# Sheet1.net
KiCad netlist of a schematic drawn in Altium Designer
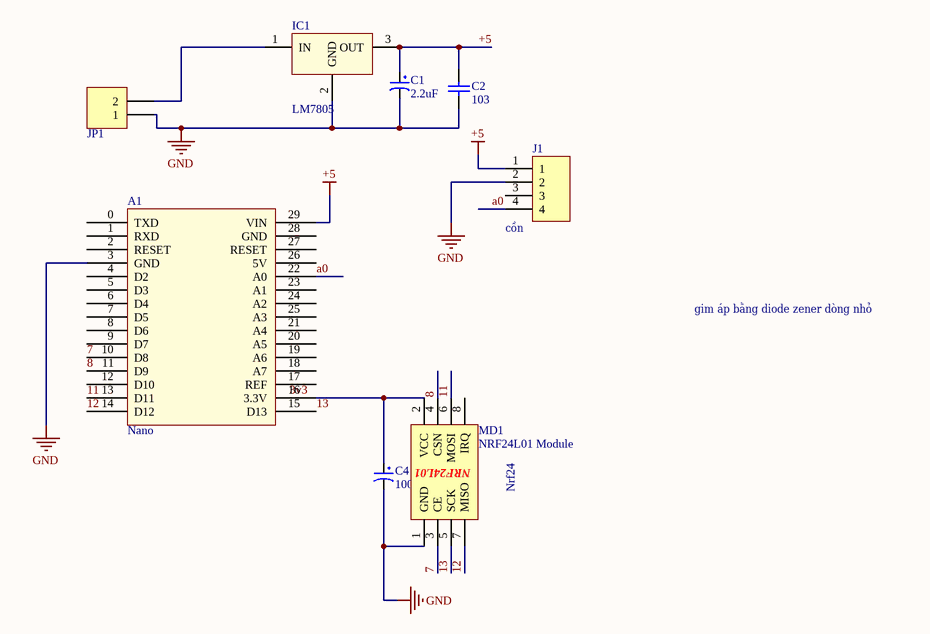
[diagram p0: Sheet1.SchDoc]

(export (version "E")
  (design (tool "Eeschema 10.0.6"))
  (components
    (comp (ref "A1")
      (value "Nano")
      (footprint "Arduino nano")
      (libsource (lib "Altium_Lib_by_KhueNguyenCreator") (part "Arduino Nano"))
    )
    (comp (ref "C1")
      (value "2.2uF")
      (footprint "tu hoa 4mm")
      (description "Cắm")
      (libsource (lib "Altium_Lib_by_KhueNguyenCreator") (part "Tu Hoa 2.2uF 50V 4x7"))
    )
    (comp (ref "C2")
      (value "103")
      (footprint "tu gom")
      (description "Cắm")
      (libsource (lib "Altium_Lib_by_KhueNguyenCreator") (part "Tu gom 103 50V"))
    )
    (comp (ref "C4")
      (value "100uF")
      (footprint "tu hoa 6.5mm")
      (description "Cắm")
      (libsource (lib "Altium_Lib_by_KhueNguyenCreator") (part "Tu Hoa 100uF 35V 6x8"))
    )
    (comp (ref "IC1")
      (value "LM7805")
      (footprint "QTO-220")
      (description "On ap +, from + 5 to + 24VDC")
      (libsource (lib "syhaunguyen") (part "LM78xx"))
    )
    (comp (ref "J1")
      (value "~")
      (footprint "CON4_50_653004117322_TH_RA")
      (description "4 Pins, 1 Row 1.25mm Pitch, right angle Connector, male")
      (fields (field (name "MANUFACTURER PART NUMBER") "653004117322") (field (name "MANUFACTURER") "JST"))
      (libsource (lib "Altium_Lib_by_KhueNguyenCreator") (part "CON-PLG_4X1-50-RA-TH"))
    )
    (comp (ref "JP1")
      (value "Header 2_1")
      (footprint "HED2")
      (description "Header, 2-Pin")
      (fields (field (name "MANUFACTURER") "Generic Components"))
      (libsource (lib "syhaunguyen") (part "Header 2_1"))
    )
    (comp (ref "MD1")
      (value "NRF24L01 Module")
      (footprint "NRF24L01")
      (libsource (lib "Altium_Lib_by_KhueNguyenCreator") (part "NRF24L01 Module"))
    )
  )
  (nets
    (net (code "1") (name "+5") (class "Default")
      (node (ref "A1") (pin "29") (pinfunction "VIN_29") (pintype "passive"))
      (node (ref "C1") (pin "1") (pinfunction "1_1") (pintype "passive"))
      (node (ref "C2") (pin "1") (pinfunction "1_1") (pintype "passive"))
      (node (ref "IC1") (pin "3") (pinfunction "OUT_3") (pintype "passive"))
      (node (ref "J1") (pin "1") (pinfunction "1_1") (pintype "passive"))
    )
    (net (code "3") (name "/7") (class "Default")
      (node (ref "A1") (pin "10") (pinfunction "D8_10") (pintype "passive"))
      (node (ref "MD1") (pin "3") (pinfunction "CE_3") (pintype "passive"))
    )
    (net (code "4") (name "/8") (class "Default")
      (node (ref "A1") (pin "11") (pinfunction "D9_11") (pintype "passive"))
      (node (ref "MD1") (pin "4") (pinfunction "CSN_4") (pintype "passive"))
    )
    (net (code "5") (name "/11") (class "Default")
      (node (ref "A1") (pin "13") (pinfunction "D11_13") (pintype "passive"))
      (node (ref "MD1") (pin "6") (pinfunction "MOSI_6") (pintype "passive"))
    )
    (net (code "6") (name "/12") (class "Default")
      (node (ref "A1") (pin "14") (pinfunction "D12_14") (pintype "passive"))
      (node (ref "MD1") (pin "7") (pinfunction "MISO_7") (pintype "passive"))
    )
    (net (code "7") (name "/13") (class "Default")
      (node (ref "A1") (pin "15") (pinfunction "D13_15") (pintype "passive"))
      (node (ref "MD1") (pin "5") (pinfunction "SCK_5") (pintype "passive"))
    )
    (net (code "8") (name "/a0") (class "Default")
      (node (ref "A1") (pin "22") (pinfunction "A0_22") (pintype "passive"))
      (node (ref "J1") (pin "4") (pinfunction "4_4") (pintype "passive"))
    )
    (net (code "9") (name "GND") (class "Default")
      (node (ref "A1") (pin "3") (pinfunction "GND_3") (pintype "passive"))
      (node (ref "C1") (pin "2") (pinfunction "2_2") (pintype "passive"))
      (node (ref "C2") (pin "2") (pinfunction "2_2") (pintype "passive"))
      (node (ref "C4") (pin "2") (pinfunction "2_2") (pintype "passive"))
      (node (ref "IC1") (pin "2") (pinfunction "GND_2") (pintype "passive"))
      (node (ref "J1") (pin "2") (pinfunction "2_2") (pintype "passive"))
      (node (ref "JP1") (pin "1") (pinfunction "1_1") (pintype "passive"))
      (node (ref "MD1") (pin "1") (pinfunction "GND_1") (pintype "passive"))
    )
    (net (code "10") (name "Net-(A1-3.3V)") (class "Default")
      (node (ref "A1") (pin "16") (pinfunction "3.3V_16") (pintype "passive"))
      (node (ref "C4") (pin "1") (pinfunction "1_1") (pintype "passive"))
      (node (ref "MD1") (pin "2") (pinfunction "VCC_2") (pintype "passive"))
    )
    (net (code "11") (name "Net-(IC1-IN)") (class "Default")
      (node (ref "IC1") (pin "1") (pinfunction "IN_1") (pintype "passive"))
      (node (ref "JP1") (pin "2") (pinfunction "2_2") (pintype "passive"))
    )
    (net (code "12") (name "unconnected-(A1-5V-Pad26)") (class "Default")
      (node (ref "A1") (pin "26") (pinfunction "5V_26") (pintype "passive"))
    )
    (net (code "13") (name "unconnected-(A1-A1-Pad23)") (class "Default")
      (node (ref "A1") (pin "23") (pinfunction "A1_23") (pintype "passive"))
    )
    (net (code "14") (name "unconnected-(A1-A2-Pad24)") (class "Default")
      (node (ref "A1") (pin "24") (pinfunction "A2_24") (pintype "passive"))
    )
    (net (code "15") (name "unconnected-(A1-A3-Pad25)") (class "Default")
      (node (ref "A1") (pin "25") (pinfunction "A3_25") (pintype "passive"))
    )
    (net (code "16") (name "unconnected-(A1-A4-Pad21)") (class "Default")
      (node (ref "A1") (pin "21") (pinfunction "A4_21") (pintype "passive"))
    )
    (net (code "17") (name "unconnected-(A1-A5-Pad20)") (class "Default")
      (node (ref "A1") (pin "20") (pinfunction "A5_20") (pintype "passive"))
    )
    (net (code "18") (name "unconnected-(A1-A6-Pad19)") (class "Default")
      (node (ref "A1") (pin "19") (pinfunction "A6_19") (pintype "passive"))
    )
    (net (code "19") (name "unconnected-(A1-A7-Pad18)") (class "Default")
      (node (ref "A1") (pin "18") (pinfunction "A7_18") (pintype "passive"))
    )
    (net (code "20") (name "unconnected-(A1-D2-Pad4)") (class "Default")
      (node (ref "A1") (pin "4") (pinfunction "D2_4") (pintype "passive"))
    )
    (net (code "21") (name "unconnected-(A1-D3-Pad5)") (class "Default")
      (node (ref "A1") (pin "5") (pinfunction "D3_5") (pintype "passive"))
    )
    (net (code "22") (name "unconnected-(A1-D4-Pad6)") (class "Default")
      (node (ref "A1") (pin "6") (pinfunction "D4_6") (pintype "passive"))
    )
    (net (code "23") (name "unconnected-(A1-D5-Pad7)") (class "Default")
      (node (ref "A1") (pin "7") (pinfunction "D5_7") (pintype "passive"))
    )
    (net (code "24") (name "unconnected-(A1-D6-Pad8)") (class "Default")
      (node (ref "A1") (pin "8") (pinfunction "D6_8") (pintype "passive"))
    )
    (net (code "25") (name "unconnected-(A1-D7-Pad9)") (class "Default")
      (node (ref "A1") (pin "9") (pinfunction "D7_9") (pintype "passive"))
    )
    (net (code "26") (name "unconnected-(A1-D10-Pad12)") (class "Default")
      (node (ref "A1") (pin "12") (pinfunction "D10_12") (pintype "passive"))
    )
    (net (code "27") (name "unconnected-(A1-GND-Pad28)") (class "Default")
      (node (ref "A1") (pin "28") (pinfunction "GND_28") (pintype "passive"))
    )
    (net (code "28") (name "unconnected-(A1-REF-Pad17)") (class "Default")
      (node (ref "A1") (pin "17") (pinfunction "REF_17") (pintype "passive"))
    )
    (net (code "29") (name "unconnected-(A1-RESET-Pad2)") (class "Default")
      (node (ref "A1") (pin "2") (pinfunction "RESET_2") (pintype "passive"))
    )
    (net (code "30") (name "unconnected-(A1-RESET-Pad27)") (class "Default")
      (node (ref "A1") (pin "27") (pinfunction "RESET_27") (pintype "passive"))
    )
    (net (code "31") (name "unconnected-(A1-RXD-Pad1)") (class "Default")
      (node (ref "A1") (pin "1") (pinfunction "RXD_1") (pintype "passive"))
    )
    (net (code "32") (name "unconnected-(A1-TXD-Pad0)") (class "Default")
      (node (ref "A1") (pin "0") (pinfunction "TXD_0") (pintype "passive"))
    )
    (net (code "33") (name "unconnected-(J1-Pad3)") (class "Default")
      (node (ref "J1") (pin "3") (pinfunction "3_3") (pintype "passive"))
    )
    (net (code "34") (name "unconnected-(MD1-IRQ-Pad8)") (class "Default")
      (node (ref "MD1") (pin "8") (pinfunction "IRQ_8") (pintype "passive"))
    )
  )
)
